# m1284p-40p-breakout_board.net
KiCad netlist of a schematic drawn in EAGLE
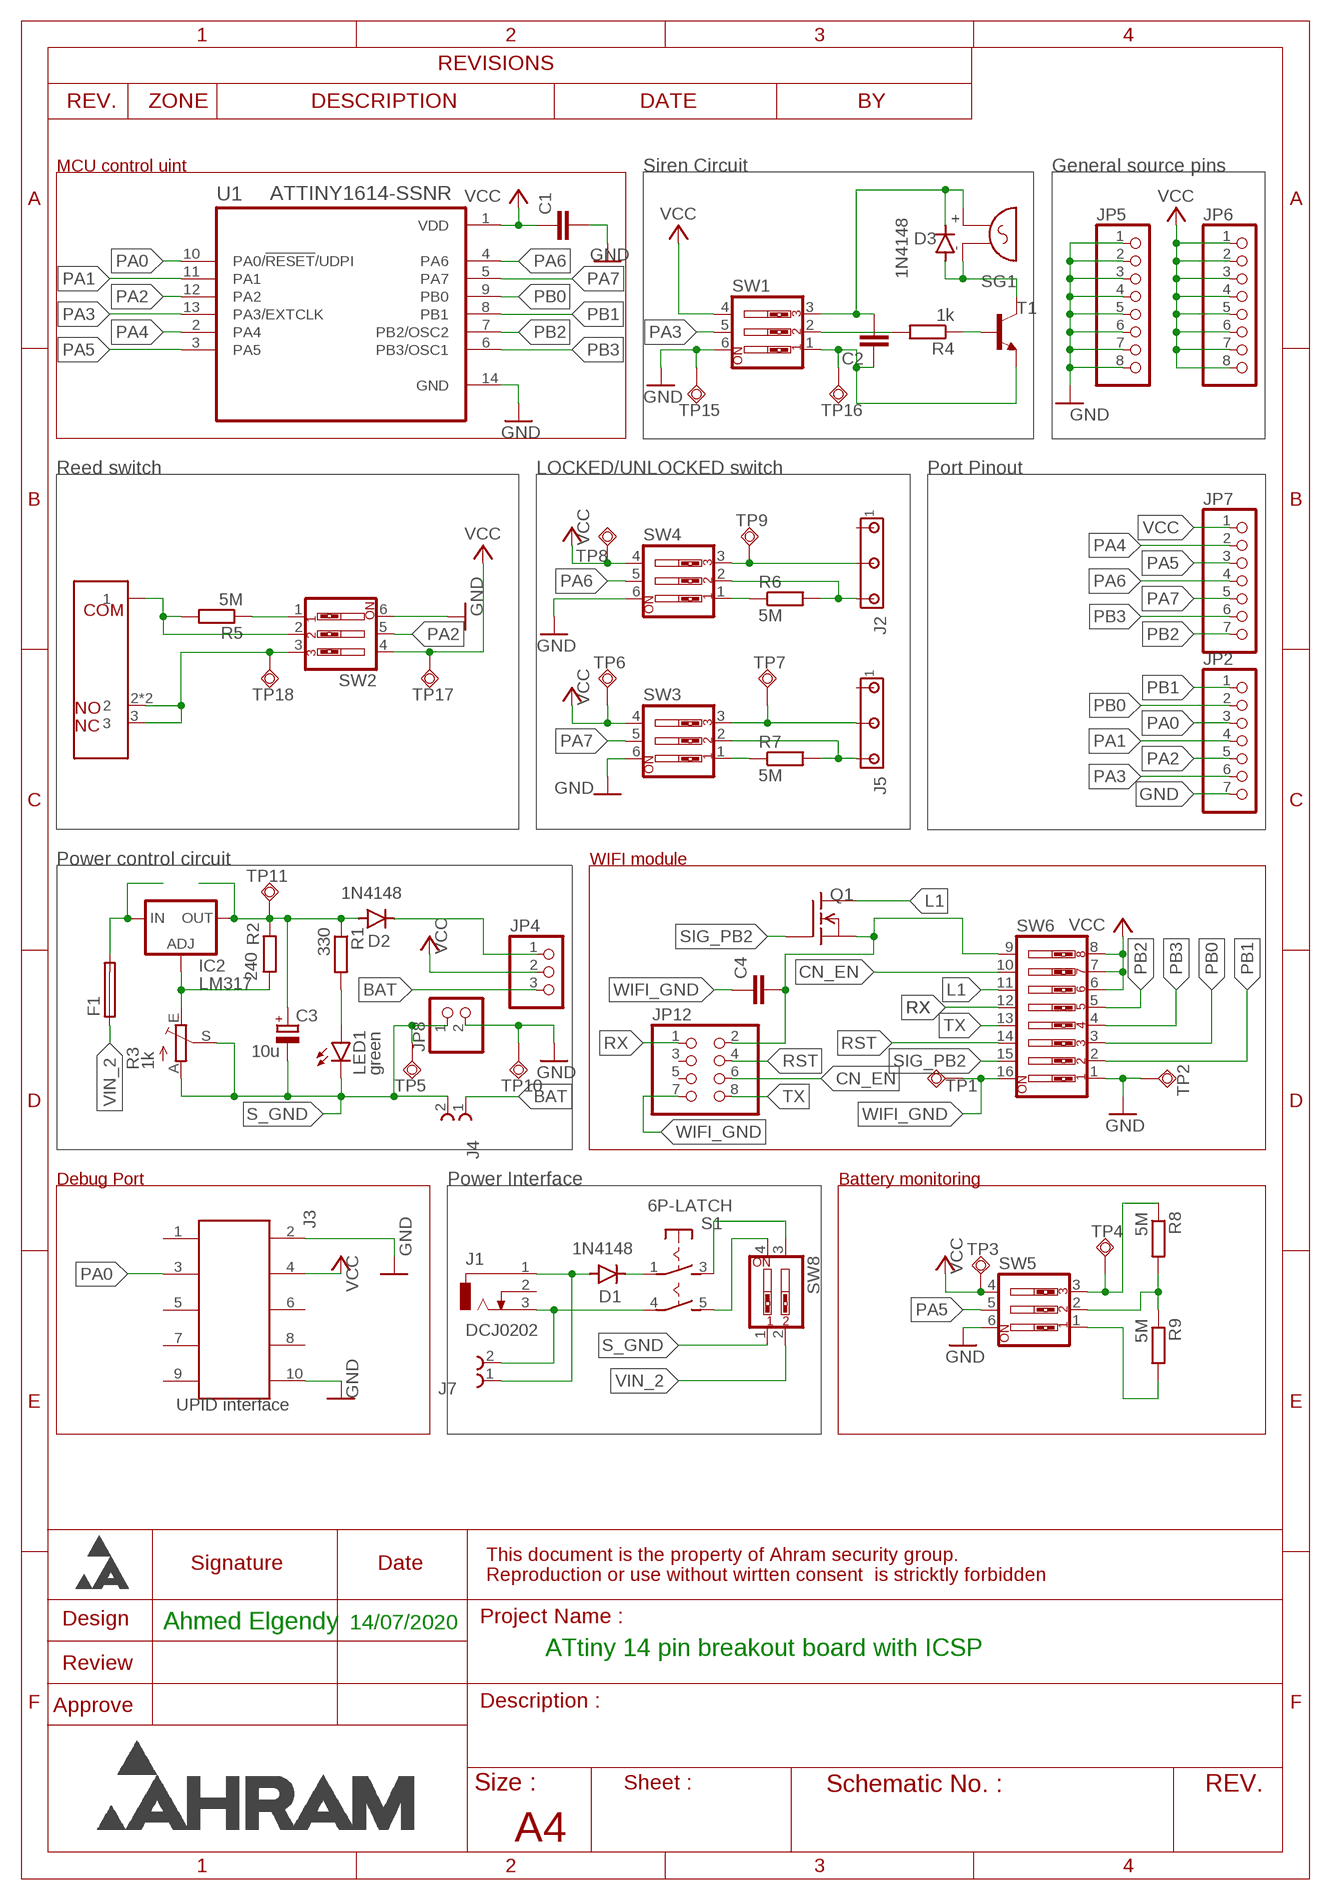
[diagram p0: schematic, sheet 1]

(export (version "E")
  (design (tool "Eeschema 10.0.6"))
  (components
    (comp (ref "C1")
      (value "C-EU025-030X050")
      (footprint "eagle-import:C025-030X050")
      (libsource (lib "eagle-import") (part "C-EU025-030X050"))
    )
    (comp (ref "C2")
      (value "C-EU025-030X050")
      (footprint "eagle-import:C025-030X050")
      (libsource (lib "eagle-import") (part "C-EU025-030X050"))
    )
    (comp (ref "C3")
      (value "10u")
      (footprint "eagle-import:E2-4")
      (libsource (lib "eagle-import") (part "CPOL-EUE2-4"))
    )
    (comp (ref "C4")
      (value "C-EU025-030X050")
      (footprint "eagle-import:C025-030X050")
      (libsource (lib "eagle-import") (part "C-EU025-030X050"))
    )
    (comp (ref "D1")
      (value "1N4148")
      (footprint "eagle-import:DO35-7")
      (libsource (lib "eagle-import") (part "1N4148DO35-7"))
    )
    (comp (ref "D2")
      (value "1N4148")
      (footprint "eagle-import:DO35-7")
      (libsource (lib "eagle-import") (part "1N4148DO35-7"))
    )
    (comp (ref "D3")
      (value "1N4148")
      (footprint "eagle-import:DO35-7")
      (libsource (lib "eagle-import") (part "1N4148DO35-7"))
    )
    (comp (ref "F1")
      (value "SH22,5A")
      (footprint "eagle-import:SH22,5A")
      (fields (field (name "MPN") "0031.7701.11"))
      (libsource (lib "eagle-import") (part "SH22,5A"))
    )
    (comp (ref "IC2")
      (value "LM317")
      (footprint "eagle-import:317TS")
      (libsource (lib "eagle-import") (part "LM317TS"))
    )
    (comp (ref "J1")
      (value "DCJ0202")
      (footprint "eagle-import:DCJ0202")
      (libsource (lib "eagle-import") (part "DCJ0202"))
    )
    (comp (ref "J2")
      (value "MTA05-156_MYVSPACE1")
      (footprint "eagle-import:10X05MTA_MYV")
      (libsource (lib "eagle-import") (part "MTA05-156_MYVSPACE1"))
    )
    (comp (ref "J3")
      (value "UPID interface")
      (footprint "eagle-import:612010235121")
      (libsource (lib "eagle-import") (part "612010235121"))
    )
    (comp (ref "J4")
      (value "691101710002")
      (footprint "eagle-import:691101710002")
      (libsource (lib "eagle-import") (part "691101710002"))
    )
    (comp (ref "J5")
      (value "MTA05-156_MYVSPACE1")
      (footprint "eagle-import:10X05MTA_MYV")
      (libsource (lib "eagle-import") (part "MTA05-156_MYVSPACE1"))
    )
    (comp (ref "J7")
      (value "691101710002")
      (footprint "eagle-import:691101710002")
      (libsource (lib "eagle-import") (part "691101710002"))
    )
    (comp (ref "JP2")
      (value "PINHD-1X7")
      (footprint "eagle-import:1X07")
      (libsource (lib "eagle-import") (part "PINHD-1X7"))
    )
    (comp (ref "JP4")
      (value "PINHD-1X3")
      (footprint "eagle-import:1X03")
      (libsource (lib "eagle-import") (part "PINHD-1X3"))
    )
    (comp (ref "JP5")
      (value "PINHD-1X8")
      (footprint "eagle-import:1X08")
      (libsource (lib "eagle-import") (part "PINHD-1X8"))
    )
    (comp (ref "JP6")
      (value "PINHD-1X8")
      (footprint "eagle-import:1X08")
      (libsource (lib "eagle-import") (part "PINHD-1X8"))
    )
    (comp (ref "JP7")
      (value "PINHD-1X7")
      (footprint "eagle-import:1X07")
      (libsource (lib "eagle-import") (part "PINHD-1X7"))
    )
    (comp (ref "JP8")
      (value "PINHD-1X2")
      (footprint "eagle-import:1X02")
      (libsource (lib "eagle-import") (part "PINHD-1X2"))
    )
    (comp (ref "JP12")
      (value "PINHD-2X4")
      (footprint "eagle-import:2X04")
      (libsource (lib "eagle-import") (part "PINHD-2X4"))
    )
    (comp (ref "LED1")
      (value "green")
      (footprint "eagle-import:LED3MM")
      (libsource (lib "eagle-import") (part "LED3MM"))
    )
    (comp (ref "Q1")
      (value "BSS295")
      (footprint "eagle-import:TO92")
      (libsource (lib "eagle-import") (part "BSS295"))
    )
    (comp (ref "R1")
      (value "330")
      (footprint "eagle-import:0204_7")
      (libsource (lib "eagle-import") (part "R-EU_0204/7"))
    )
    (comp (ref "R2")
      (value "240")
      (footprint "eagle-import:0204_7")
      (libsource (lib "eagle-import") (part "R-EU_0204/7"))
    )
    (comp (ref "R3")
      (value "1k")
      (footprint "eagle-import:RJ9W")
      (libsource (lib "eagle-import") (part "TRIM_EU-RJ9W"))
    )
    (comp (ref "R4")
      (value "1k")
      (footprint "eagle-import:0204_7")
      (libsource (lib "eagle-import") (part "R-EU_0204/7"))
    )
    (comp (ref "R5")
      (value "5M")
      (footprint "eagle-import:0204_7")
      (libsource (lib "eagle-import") (part "R-EU_0204/7"))
    )
    (comp (ref "R6")
      (value "5M")
      (footprint "eagle-import:0204_7")
      (libsource (lib "eagle-import") (part "R-EU_0204/7"))
    )
    (comp (ref "R7")
      (value "5M")
      (footprint "eagle-import:0204_7")
      (libsource (lib "eagle-import") (part "R-EU_0204/7"))
    )
    (comp (ref "R8")
      (value "5M")
      (footprint "eagle-import:0204_7")
      (libsource (lib "eagle-import") (part "R-EU_0204/7"))
    )
    (comp (ref "R9")
      (value "5M")
      (footprint "eagle-import:0204_7")
      (libsource (lib "eagle-import") (part "R-EU_0204/7"))
    )
    (comp (ref "S1")
      (value "6P-LATCH")
      (footprint "eagle-import:TACT-6P-LATCH")
      (libsource (lib "eagle-import") (part "6P-LATCH"))
    )
    (comp (ref "S2")
      (value "REED_1513")
      (footprint "eagle-import:REED_MYV")
      (libsource (lib "eagle-import") (part "REED_1513"))
    )
    (comp (ref "SG1")
      (value "F/QMX")
      (footprint "eagle-import:F_QMX")
      (libsource (lib "eagle-import") (part "F/QMX"))
    )
    (comp (ref "SW1")
      (value "SW_DIP-3")
      (footprint "eagle-import:EDG-03")
      (libsource (lib "eagle-import") (part "SW_DIP-3"))
    )
    (comp (ref "SW2")
      (value "SW_DIP-3")
      (footprint "eagle-import:EDG-03")
      (libsource (lib "eagle-import") (part "SW_DIP-3"))
    )
    (comp (ref "SW3")
      (value "SW_DIP-3")
      (footprint "eagle-import:EDG-03")
      (libsource (lib "eagle-import") (part "SW_DIP-3"))
    )
    (comp (ref "SW4")
      (value "SW_DIP-3")
      (footprint "eagle-import:EDG-03")
      (libsource (lib "eagle-import") (part "SW_DIP-3"))
    )
    (comp (ref "SW5")
      (value "SW_DIP-3")
      (footprint "eagle-import:EDG-03")
      (libsource (lib "eagle-import") (part "SW_DIP-3"))
    )
    (comp (ref "SW6")
      (value "SW_DIP-8")
      (footprint "eagle-import:EDG-08")
      (libsource (lib "eagle-import") (part "SW_DIP-8"))
    )
    (comp (ref "SW8")
      (value "SW_DIP-2")
      (footprint "eagle-import:EDG-02")
      (libsource (lib "eagle-import") (part "SW_DIP-2"))
    )
    (comp (ref "T1")
      (value "2N2222")
      (footprint "eagle-import:TO18")
      (libsource (lib "eagle-import") (part "2N2222"))
    )
    (comp (ref "TP1")
      (value "TPSQPAD1-13")
      (footprint "eagle-import:P1-13")
      (libsource (lib "eagle-import") (part "TPSQPAD1-13"))
    )
    (comp (ref "TP2")
      (value "TPSQPAD1-13")
      (footprint "eagle-import:P1-13")
      (libsource (lib "eagle-import") (part "TPSQPAD1-13"))
    )
    (comp (ref "TP3")
      (value "TPSQPAD1-13")
      (footprint "eagle-import:P1-13")
      (libsource (lib "eagle-import") (part "TPSQPAD1-13"))
    )
    (comp (ref "TP4")
      (value "TPSQPAD1-13")
      (footprint "eagle-import:P1-13")
      (libsource (lib "eagle-import") (part "TPSQPAD1-13"))
    )
    (comp (ref "TP5")
      (value "TPSQPAD1-13")
      (footprint "eagle-import:P1-13")
      (libsource (lib "eagle-import") (part "TPSQPAD1-13"))
    )
    (comp (ref "TP6")
      (value "TPSQPAD1-13")
      (footprint "eagle-import:P1-13")
      (libsource (lib "eagle-import") (part "TPSQPAD1-13"))
    )
    (comp (ref "TP7")
      (value "TPSQPAD1-13")
      (footprint "eagle-import:P1-13")
      (libsource (lib "eagle-import") (part "TPSQPAD1-13"))
    )
    (comp (ref "TP8")
      (value "TPSQPAD1-13")
      (footprint "eagle-import:P1-13")
      (libsource (lib "eagle-import") (part "TPSQPAD1-13"))
    )
    (comp (ref "TP9")
      (value "TPSQPAD1-13")
      (footprint "eagle-import:P1-13")
      (libsource (lib "eagle-import") (part "TPSQPAD1-13"))
    )
    (comp (ref "TP10")
      (value "TPSQPAD1-13")
      (footprint "eagle-import:P1-13")
      (libsource (lib "eagle-import") (part "TPSQPAD1-13"))
    )
    (comp (ref "TP11")
      (value "TPSQPAD1-13")
      (footprint "eagle-import:P1-13")
      (libsource (lib "eagle-import") (part "TPSQPAD1-13"))
    )
    (comp (ref "TP15")
      (value "TPSQPAD1-13")
      (footprint "eagle-import:P1-13")
      (libsource (lib "eagle-import") (part "TPSQPAD1-13"))
    )
    (comp (ref "TP16")
      (value "TPSQPAD1-13")
      (footprint "eagle-import:P1-13")
      (libsource (lib "eagle-import") (part "TPSQPAD1-13"))
    )
    (comp (ref "TP17")
      (value "TPSQPAD1-13")
      (footprint "eagle-import:P1-13")
      (libsource (lib "eagle-import") (part "TPSQPAD1-13"))
    )
    (comp (ref "TP18")
      (value "TPSQPAD1-13")
      (footprint "eagle-import:P1-13")
      (libsource (lib "eagle-import") (part "TPSQPAD1-13"))
    )
    (comp (ref "U1")
      (value "ATTINY1614-SSNR")
      (footprint "eagle-import:SOIC127P600X175-14N")
      (fields (field (name "MF") "Microchip Technology"))
      (libsource (lib "eagle-import") (part "ATTINY1614-SSNR"))
    )
  )
  (nets
    (net (code "1") (name "BAT") (class "Default")
      (node (ref "J4") (pin "1") (pinfunction "1_1") (pintype "passive"))
      (node (ref "JP4") (pin "3") (pinfunction "3_3") (pintype "passive"))
    )
    (net (code "2") (name "CN_EN") (class "Default")
      (node (ref "JP12") (pin "6") (pinfunction "6_6") (pintype "passive"))
      (node (ref "SW6") (pin "10") (pinfunction "10_10") (pintype "passive"))
    )
    (net (code "3") (name "GND") (class "Default")
      (node (ref "C1") (pin "2") (pinfunction "2_2") (pintype "passive"))
      (node (ref "J3") (pin "10") (pinfunction "10_10") (pintype "passive"))
      (node (ref "J3") (pin "2") (pinfunction "2_2") (pintype "passive"))
      (node (ref "JP2") (pin "7") (pinfunction "7_7") (pintype "passive"))
      (node (ref "JP5") (pin "1") (pinfunction "1_1") (pintype "passive"))
      (node (ref "JP5") (pin "2") (pinfunction "2_2") (pintype "passive"))
      (node (ref "JP5") (pin "3") (pinfunction "3_3") (pintype "passive"))
      (node (ref "JP5") (pin "4") (pinfunction "4_4") (pintype "passive"))
      (node (ref "JP5") (pin "5") (pinfunction "5_5") (pintype "passive"))
      (node (ref "JP5") (pin "6") (pinfunction "6_6") (pintype "passive"))
      (node (ref "JP5") (pin "7") (pinfunction "7_7") (pintype "passive"))
      (node (ref "JP5") (pin "8") (pinfunction "8_8") (pintype "passive"))
      (node (ref "JP8") (pin "2") (pinfunction "2_2") (pintype "passive"))
      (node (ref "SW1") (pin "6") (pinfunction "6_6") (pintype "passive"))
      (node (ref "SW2") (pin "6") (pinfunction "6_6") (pintype "passive"))
      (node (ref "SW3") (pin "6") (pinfunction "6_6") (pintype "passive"))
      (node (ref "SW4") (pin "6") (pinfunction "6_6") (pintype "passive"))
      (node (ref "SW5") (pin "6") (pinfunction "6_6") (pintype "passive"))
      (node (ref "SW6") (pin "1") (pinfunction "1_1") (pintype "passive"))
      (node (ref "TP10") (pin "TP") (pinfunction "TP_TP") (pintype "input"))
      (node (ref "TP15") (pin "TP") (pinfunction "TP_TP") (pintype "input"))
      (node (ref "TP2") (pin "TP") (pinfunction "TP_TP") (pintype "input"))
      (node (ref "U1") (pin "14") (pinfunction "GND_14") (pintype "power_in"))
    )
    (net (code "4") (name "L1") (class "Default")
      (node (ref "Q1") (pin "3") (pinfunction "D_3") (pintype "passive"))
      (node (ref "SW6") (pin "11") (pinfunction "11_11") (pintype "passive"))
    )
    (net (code "5") (name "Net-(D1-PadA)") (class "Default")
      (node (ref "D1") (pin "A") (pinfunction "A_A") (pintype "passive"))
      (node (ref "J1") (pin "1") (pinfunction "1_1") (pintype "passive"))
      (node (ref "J7") (pin "1") (pinfunction "1_1") (pintype "passive"))
    )
    (net (code "6") (name "Net-(D1-PadC)") (class "Default")
      (node (ref "D1") (pin "C") (pinfunction "C_C") (pintype "passive"))
      (node (ref "S1") (pin "1") (pinfunction "1_1") (pintype "bidirectional"))
    )
    (net (code "7") (name "Net-(D2-PadC)") (class "Default")
      (node (ref "D2") (pin "C") (pinfunction "C_C") (pintype "passive"))
      (node (ref "JP4") (pin "1") (pinfunction "1_1") (pintype "passive"))
    )
    (net (code "8") (name "Net-(IC2-ADJ)") (class "Default")
      (node (ref "IC2") (pin "1") (pinfunction "ADJ_1") (pintype "input"))
      (node (ref "R2") (pin "1") (pinfunction "1_1") (pintype "passive"))
      (node (ref "R3") (pin "E") (pinfunction "E_E") (pintype "passive"))
    )
    (net (code "9") (name "Net-(IC2-IN)") (class "Default")
      (node (ref "F1") (pin "2") (pinfunction "2_2") (pintype "passive"))
      (node (ref "IC2") (pin "3") (pinfunction "IN_3") (pintype "input"))
    )
    (net (code "10") (name "Net-(IC2-OUT)") (class "Default")
      (node (ref "C3") (pin "+") (pinfunction "+_+") (pintype "passive"))
      (node (ref "D2") (pin "A") (pinfunction "A_A") (pintype "passive"))
      (node (ref "IC2") (pin "2") (pinfunction "OUT_2") (pintype "passive"))
      (node (ref "R1") (pin "1") (pinfunction "1_1") (pintype "passive"))
      (node (ref "R2") (pin "2") (pinfunction "2_2") (pintype "passive"))
      (node (ref "TP11") (pin "TP") (pinfunction "TP_TP") (pintype "input"))
    )
    (net (code "11") (name "Net-(J2-Pad3)") (class "Default")
      (node (ref "J2") (pin "3") (pinfunction "3_3") (pintype "passive"))
      (node (ref "SW4") (pin "3") (pinfunction "3_3") (pintype "passive"))
      (node (ref "TP9") (pin "TP") (pinfunction "TP_TP") (pintype "input"))
    )
    (net (code "12") (name "Net-(J2-Pad5)") (class "Default")
      (node (ref "J2") (pin "5") (pinfunction "5_5") (pintype "passive"))
      (node (ref "R6") (pin "2") (pinfunction "2_2") (pintype "passive"))
      (node (ref "SW4") (pin "2") (pinfunction "2_2") (pintype "passive"))
    )
    (net (code "13") (name "Net-(J5-Pad3)") (class "Default")
      (node (ref "J5") (pin "3") (pinfunction "3_3") (pintype "passive"))
      (node (ref "SW3") (pin "3") (pinfunction "3_3") (pintype "passive"))
      (node (ref "TP7") (pin "TP") (pinfunction "TP_TP") (pintype "input"))
    )
    (net (code "14") (name "Net-(J5-Pad5)") (class "Default")
      (node (ref "J5") (pin "5") (pinfunction "5_5") (pintype "passive"))
      (node (ref "R7") (pin "2") (pinfunction "2_2") (pintype "passive"))
      (node (ref "SW3") (pin "2") (pinfunction "2_2") (pintype "passive"))
    )
    (net (code "15") (name "Net-(LED1-PadA)") (class "Default")
      (node (ref "LED1") (pin "A") (pinfunction "A_A") (pintype "passive"))
      (node (ref "R1") (pin "2") (pinfunction "2_2") (pintype "passive"))
    )
    (net (code "16") (name "Net-(Q1-S)") (class "Default")
      (node (ref "C4") (pin "2") (pinfunction "2_2") (pintype "passive"))
      (node (ref "JP12") (pin "2") (pinfunction "2_2") (pintype "passive"))
      (node (ref "Q1") (pin "1") (pinfunction "S_1") (pintype "passive"))
      (node (ref "SW6") (pin "9") (pinfunction "9_9") (pintype "passive"))
    )
    (net (code "17") (name "Net-(R4-Pad2)") (class "Default")
      (node (ref "R4") (pin "2") (pinfunction "2_2") (pintype "passive"))
      (node (ref "SW1") (pin "2") (pinfunction "2_2") (pintype "passive"))
    )
    (net (code "18") (name "Net-(R5-Pad1)") (class "Default")
      (node (ref "R5") (pin "1") (pinfunction "1_1") (pintype "passive"))
      (node (ref "SW2") (pin "1") (pinfunction "1_1") (pintype "passive"))
    )
    (net (code "19") (name "Net-(R5-Pad2)") (class "Default")
      (node (ref "R5") (pin "2") (pinfunction "2_2") (pintype "passive"))
      (node (ref "S2") (pin "1") (pinfunction "1_1") (pintype "bidirectional"))
      (node (ref "SW2") (pin "2") (pinfunction "2_2") (pintype "passive"))
    )
    (net (code "20") (name "Net-(R6-Pad1)") (class "Default")
      (node (ref "R6") (pin "1") (pinfunction "1_1") (pintype "passive"))
      (node (ref "SW4") (pin "1") (pinfunction "1_1") (pintype "passive"))
    )
    (net (code "21") (name "Net-(R7-Pad1)") (class "Default")
      (node (ref "R7") (pin "1") (pinfunction "1_1") (pintype "passive"))
      (node (ref "SW3") (pin "1") (pinfunction "1_1") (pintype "passive"))
    )
    (net (code "22") (name "Net-(R8-Pad1)") (class "Default")
      (node (ref "R8") (pin "1") (pinfunction "1_1") (pintype "passive"))
      (node (ref "SW5") (pin "3") (pinfunction "3_3") (pintype "passive"))
      (node (ref "TP4") (pin "TP") (pinfunction "TP_TP") (pintype "input"))
    )
    (net (code "23") (name "Net-(R8-Pad2)") (class "Default")
      (node (ref "R8") (pin "2") (pinfunction "2_2") (pintype "passive"))
      (node (ref "R9") (pin "1") (pinfunction "1_1") (pintype "passive"))
      (node (ref "SW5") (pin "2") (pinfunction "2_2") (pintype "passive"))
    )
    (net (code "24") (name "Net-(R9-Pad2)") (class "Default")
      (node (ref "R9") (pin "2") (pinfunction "2_2") (pintype "passive"))
      (node (ref "SW5") (pin "1") (pinfunction "1_1") (pintype "passive"))
    )
    (net (code "25") (name "Net-(S1-2)") (class "Default")
      (node (ref "S1") (pin "3") (pinfunction "2_3") (pintype "bidirectional"))
      (node (ref "SW8") (pin "3") (pinfunction "3_3") (pintype "passive"))
    )
    (net (code "26") (name "Net-(S1-3)") (class "Default")
      (node (ref "J1") (pin "3") (pinfunction "3_3") (pintype "passive"))
      (node (ref "J7") (pin "2") (pinfunction "2_2") (pintype "passive"))
      (node (ref "S1") (pin "4") (pinfunction "3_4") (pintype "bidirectional"))
    )
    (net (code "27") (name "Net-(S1-4)") (class "Default")
      (node (ref "S1") (pin "5") (pinfunction "4_5") (pintype "bidirectional"))
      (node (ref "SW8") (pin "4") (pinfunction "4_4") (pintype "passive"))
    )
    (net (code "28") (name "Net-(S2-2-Pad4)") (class "Default")
      (node (ref "S2") (pin "2") (pinfunction "2_2") (pintype "bidirectional"))
      (node (ref "S2") (pin "3") (pinfunction "3_3") (pintype "bidirectional"))
      (node (ref "S2") (pin "4") (pinfunction "2_4") (pintype "bidirectional"))
      (node (ref "SW2") (pin "3") (pinfunction "3_3") (pintype "passive"))
      (node (ref "TP18") (pin "TP") (pinfunction "TP_TP") (pintype "input"))
    )
    (net (code "29") (name "Net-(SG1-1)") (class "Default")
      (node (ref "D3") (pin "A") (pinfunction "A_A") (pintype "passive"))
      (node (ref "SG1") (pin "-") (pinfunction "1_-") (pintype "passive"))
      (node (ref "T1") (pin "3") (pinfunction "C_3") (pintype "passive"))
    )
    (net (code "30") (name "Net-(SG1-2)") (class "Default")
      (node (ref "C2") (pin "2") (pinfunction "2_2") (pintype "passive"))
      (node (ref "D3") (pin "C") (pinfunction "C_C") (pintype "passive"))
      (node (ref "SG1") (pin "+") (pinfunction "2_+") (pintype "passive"))
      (node (ref "SW1") (pin "3") (pinfunction "3_3") (pintype "passive"))
    )
    (net (code "31") (name "Net-(T1-B)") (class "Default")
      (node (ref "R4") (pin "1") (pinfunction "1_1") (pintype "passive"))
      (node (ref "T1") (pin "2") (pinfunction "B_2") (pintype "passive"))
    )
    (net (code "32") (name "Net-(T1-E)") (class "Default")
      (node (ref "C2") (pin "1") (pinfunction "1_1") (pintype "passive"))
      (node (ref "SW1") (pin "1") (pinfunction "1_1") (pintype "passive"))
      (node (ref "T1") (pin "1") (pinfunction "E_1") (pintype "passive"))
      (node (ref "TP16") (pin "TP") (pinfunction "TP_TP") (pintype "input"))
    )
    (net (code "33") (name "PA0") (class "Default")
      (node (ref "J3") (pin "3") (pinfunction "3_3") (pintype "passive"))
      (node (ref "JP2") (pin "3") (pinfunction "3_3") (pintype "passive"))
      (node (ref "U1") (pin "10") (pinfunction "PA0/~{RESET}/UDPI_10") (pintype "bidirectional"))
    )
    (net (code "34") (name "PA1") (class "Default")
      (node (ref "JP2") (pin "4") (pinfunction "4_4") (pintype "passive"))
      (node (ref "U1") (pin "11") (pinfunction "PA1_11") (pintype "bidirectional"))
    )
    (net (code "35") (name "PA2") (class "Default")
      (node (ref "JP2") (pin "5") (pinfunction "5_5") (pintype "passive"))
      (node (ref "SW2") (pin "5") (pinfunction "5_5") (pintype "passive"))
      (node (ref "U1") (pin "12") (pinfunction "PA2_12") (pintype "bidirectional"))
    )
    (net (code "36") (name "PA3") (class "Default")
      (node (ref "JP2") (pin "6") (pinfunction "6_6") (pintype "passive"))
      (node (ref "SW1") (pin "5") (pinfunction "5_5") (pintype "passive"))
      (node (ref "U1") (pin "13") (pinfunction "PA3/EXTCLK_13") (pintype "bidirectional"))
    )
    (net (code "37") (name "PA4") (class "Default")
      (node (ref "JP7") (pin "2") (pinfunction "2_2") (pintype "passive"))
      (node (ref "U1") (pin "2") (pinfunction "PA4_2") (pintype "bidirectional"))
    )
    (net (code "38") (name "PA5") (class "Default")
      (node (ref "JP7") (pin "3") (pinfunction "3_3") (pintype "passive"))
      (node (ref "SW5") (pin "5") (pinfunction "5_5") (pintype "passive"))
      (node (ref "U1") (pin "3") (pinfunction "PA5_3") (pintype "bidirectional"))
    )
    (net (code "39") (name "PA6") (class "Default")
      (node (ref "JP7") (pin "4") (pinfunction "4_4") (pintype "passive"))
      (node (ref "SW4") (pin "5") (pinfunction "5_5") (pintype "passive"))
      (node (ref "U1") (pin "4") (pinfunction "PA6_4") (pintype "bidirectional"))
    )
    (net (code "40") (name "PA7") (class "Default")
      (node (ref "JP7") (pin "5") (pinfunction "5_5") (pintype "passive"))
      (node (ref "SW3") (pin "5") (pinfunction "5_5") (pintype "passive"))
      (node (ref "U1") (pin "5") (pinfunction "PA7_5") (pintype "bidirectional"))
    )
    (net (code "41") (name "PB0") (class "Default")
      (node (ref "JP2") (pin "2") (pinfunction "2_2") (pintype "passive"))
      (node (ref "SW6") (pin "3") (pinfunction "3_3") (pintype "passive"))
      (node (ref "U1") (pin "9") (pinfunction "PB0_9") (pintype "bidirectional"))
    )
    (net (code "42") (name "PB1") (class "Default")
      (node (ref "JP2") (pin "1") (pinfunction "1_1") (pintype "passive"))
      (node (ref "SW6") (pin "2") (pinfunction "2_2") (pintype "passive"))
      (node (ref "U1") (pin "8") (pinfunction "PB1_8") (pintype "bidirectional"))
    )
    (net (code "43") (name "PB2") (class "Default")
      (node (ref "JP7") (pin "7") (pinfunction "7_7") (pintype "passive"))
      (node (ref "SW6") (pin "5") (pinfunction "5_5") (pintype "passive"))
      (node (ref "U1") (pin "7") (pinfunction "PB2/OSC2_7") (pintype "bidirectional"))
    )
    (net (code "44") (name "PB3") (class "Default")
      (node (ref "JP7") (pin "6") (pinfunction "6_6") (pintype "passive"))
      (node (ref "SW6") (pin "4") (pinfunction "4_4") (pintype "passive"))
      (node (ref "U1") (pin "6") (pinfunction "PB3/OSC1_6") (pintype "bidirectional"))
    )
    (net (code "45") (name "RST") (class "Default")
      (node (ref "JP12") (pin "4") (pinfunction "4_4") (pintype "passive"))
      (node (ref "SW6") (pin "14") (pinfunction "14_14") (pintype "passive"))
    )
    (net (code "46") (name "RX") (class "Default")
      (node (ref "JP12") (pin "1") (pinfunction "1_1") (pintype "passive"))
      (node (ref "SW6") (pin "12") (pinfunction "12_12") (pintype "passive"))
    )
    (net (code "47") (name "SIG_PB2") (class "Default")
      (node (ref "Q1") (pin "2") (pinfunction "G_2") (pintype "passive"))
      (node (ref "SW6") (pin "15") (pinfunction "15_15") (pintype "passive"))
    )
    (net (code "48") (name "S_GND") (class "Default")
      (node (ref "C3") (pin "-") (pinfunction "-_-") (pintype "passive"))
      (node (ref "J4") (pin "2") (pinfunction "2_2") (pintype "passive"))
      (node (ref "JP8") (pin "1") (pinfunction "1_1") (pintype "passive"))
      (node (ref "LED1") (pin "K") (pinfunction "C_K") (pintype "passive"))
      (node (ref "R3") (pin "A") (pinfunction "A_A") (pintype "passive"))
      (node (ref "R3") (pin "S") (pinfunction "S_S") (pintype "passive"))
      (node (ref "SW8") (pin "1") (pinfunction "1_1") (pintype "passive"))
      (node (ref "TP5") (pin "TP") (pinfunction "TP_TP") (pintype "input"))
    )
    (net (code "49") (name "TX") (class "Default")
      (node (ref "JP12") (pin "8") (pinfunction "8_8") (pintype "passive"))
      (node (ref "SW6") (pin "13") (pinfunction "13_13") (pintype "passive"))
    )
    (net (code "50") (name "VCC") (class "Default")
      (node (ref "C1") (pin "1") (pinfunction "1_1") (pintype "passive"))
      (node (ref "J3") (pin "4") (pinfunction "4_4") (pintype "passive"))
      (node (ref "JP4") (pin "2") (pinfunction "2_2") (pintype "passive"))
      (node (ref "JP6") (pin "1") (pinfunction "1_1") (pintype "passive"))
      (node (ref "JP6") (pin "2") (pinfunction "2_2") (pintype "passive"))
      (node (ref "JP6") (pin "3") (pinfunction "3_3") (pintype "passive"))
      (node (ref "JP6") (pin "4") (pinfunction "4_4") (pintype "passive"))
      (node (ref "JP6") (pin "5") (pinfunction "5_5") (pintype "passive"))
      (node (ref "JP6") (pin "6") (pinfunction "6_6") (pintype "passive"))
      (node (ref "JP6") (pin "7") (pinfunction "7_7") (pintype "passive"))
      (node (ref "JP6") (pin "8") (pinfunction "8_8") (pintype "passive"))
      (node (ref "JP7") (pin "1") (pinfunction "1_1") (pintype "passive"))
      (node (ref "SW1") (pin "4") (pinfunction "4_4") (pintype "passive"))
      (node (ref "SW2") (pin "4") (pinfunction "4_4") (pintype "passive"))
      (node (ref "SW3") (pin "4") (pinfunction "4_4") (pintype "passive"))
      (node (ref "SW4") (pin "4") (pinfunction "4_4") (pintype "passive"))
      (node (ref "SW5") (pin "4") (pinfunction "4_4") (pintype "passive"))
      (node (ref "SW6") (pin "6") (pinfunction "6_6") (pintype "passive"))
      (node (ref "SW6") (pin "7") (pinfunction "7_7") (pintype "passive"))
      (node (ref "SW6") (pin "8") (pinfunction "8_8") (pintype "passive"))
      (node (ref "TP17") (pin "TP") (pinfunction "TP_TP") (pintype "input"))
      (node (ref "TP3") (pin "TP") (pinfunction "TP_TP") (pintype "input"))
      (node (ref "TP6") (pin "TP") (pinfunction "TP_TP") (pintype "input"))
      (node (ref "TP8") (pin "TP") (pinfunction "TP_TP") (pintype "input"))
      (node (ref "U1") (pin "1") (pinfunction "VDD_1") (pintype "power_in"))
    )
    (net (code "51") (name "VIN_2") (class "Default")
      (node (ref "F1") (pin "1") (pinfunction "1_1") (pintype "passive"))
      (node (ref "SW8") (pin "2") (pinfunction "2_2") (pintype "passive"))
    )
    (net (code "52") (name "WIFI_GND") (class "Default")
      (node (ref "C4") (pin "1") (pinfunction "1_1") (pintype "passive"))
      (node (ref "JP12") (pin "7") (pinfunction "7_7") (pintype "passive"))
      (node (ref "SW6") (pin "16") (pinfunction "16_16") (pintype "passive"))
      (node (ref "TP1") (pin "TP") (pinfunction "TP_TP") (pintype "input"))
    )
    (net (code "53") (name "unconnected-(J1-Pad2)") (class "Default")
      (node (ref "J1") (pin "2") (pinfunction "2_2") (pintype "passive"))
    )
    (net (code "54") (name "unconnected-(J2-Pad1)") (class "Default")
      (node (ref "J2") (pin "1") (pinfunction "1_1") (pintype "passive"))
    )
    (net (code "55") (name "unconnected-(J3-Pad1)") (class "Default")
      (node (ref "J3") (pin "1") (pinfunction "1_1") (pintype "passive"))
    )
    (net (code "56") (name "unconnected-(J3-Pad5)") (class "Default")
      (node (ref "J3") (pin "5") (pinfunction "5_5") (pintype "passive"))
    )
    (net (code "57") (name "unconnected-(J3-Pad6)") (class "Default")
      (node (ref "J3") (pin "6") (pinfunction "6_6") (pintype "passive"))
    )
    (net (code "58") (name "unconnected-(J3-Pad7)") (class "Default")
      (node (ref "J3") (pin "7") (pinfunction "7_7") (pintype "passive"))
    )
    (net (code "59") (name "unconnected-(J3-Pad8)") (class "Default")
      (node (ref "J3") (pin "8") (pinfunction "8_8") (pintype "passive"))
    )
    (net (code "60") (name "unconnected-(J3-Pad9)") (class "Default")
      (node (ref "J3") (pin "9") (pinfunction "9_9") (pintype "passive"))
    )
    (net (code "61") (name "unconnected-(J5-Pad1)") (class "Default")
      (node (ref "J5") (pin "1") (pinfunction "1_1") (pintype "passive"))
    )
    (net (code "62") (name "unconnected-(JP12-Pad3)") (class "Default")
      (node (ref "JP12") (pin "3") (pinfunction "3_3") (pintype "passive"))
    )
    (net (code "63") (name "unconnected-(JP12-Pad5)") (class "Default")
      (node (ref "JP12") (pin "5") (pinfunction "5_5") (pintype "passive"))
    )
  )
)
